# mainbrd.net
KiCad netlist of a schematic drawn in EAGLE
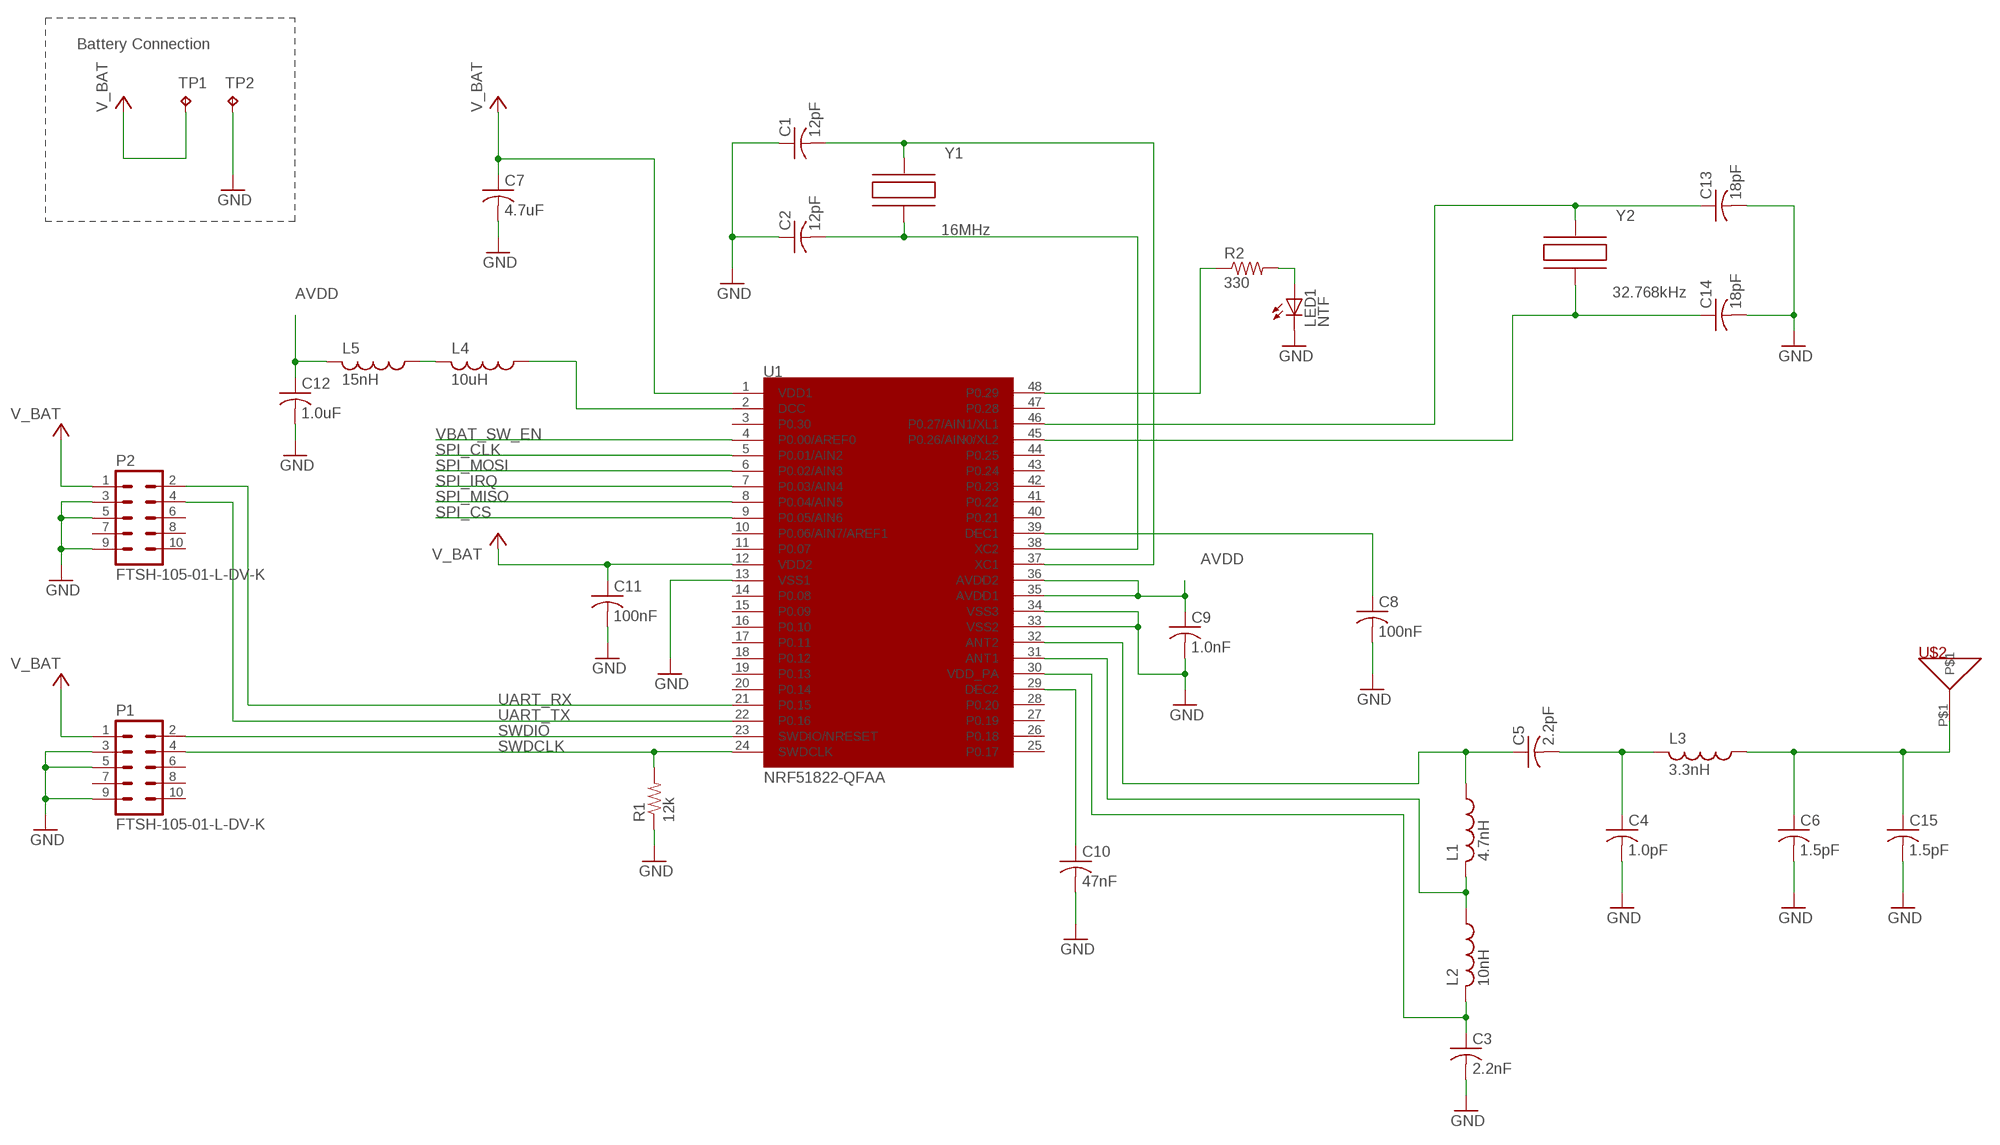
[diagram p0: schematic, sheet 1]
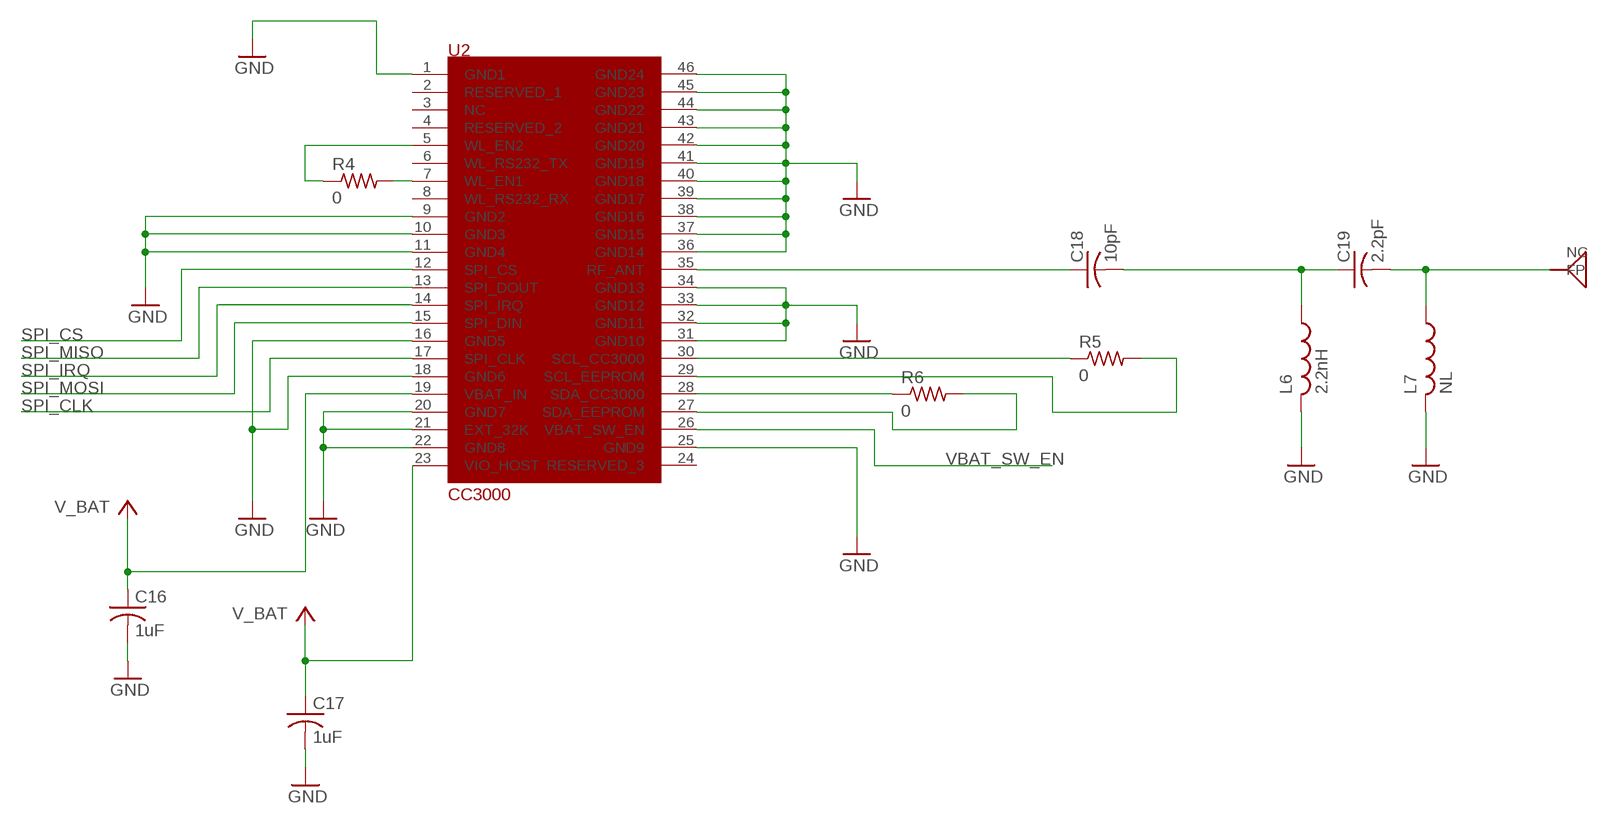
[diagram p1: schematic, sheet 2]

(export (version "E")
  (design (tool "Eeschema 10.0.6"))
  (components
    (comp (ref "C1")
      (value "12pF")
      (footprint "eagle-import:C0402")
      (libsource (lib "eagle-import") (part "C-USC0402"))
    )
    (comp (ref "C2")
      (value "12pF")
      (footprint "eagle-import:C0402")
      (libsource (lib "eagle-import") (part "C-USC0402"))
    )
    (comp (ref "C3")
      (value "2.2nF")
      (footprint "eagle-import:C0402")
      (libsource (lib "eagle-import") (part "C-USC0402"))
    )
    (comp (ref "C4")
      (value "1.0pF")
      (footprint "eagle-import:C0402")
      (libsource (lib "eagle-import") (part "C-USC0402"))
    )
    (comp (ref "C5")
      (value "2.2pF")
      (footprint "eagle-import:C0402")
      (libsource (lib "eagle-import") (part "C-USC0402"))
    )
    (comp (ref "C6")
      (value "1.5pF")
      (footprint "eagle-import:C0402")
      (libsource (lib "eagle-import") (part "C-USC0402"))
    )
    (comp (ref "C7")
      (value "4.7uF")
      (footprint "eagle-import:C0603")
      (libsource (lib "eagle-import") (part "C-USC0603"))
    )
    (comp (ref "C8")
      (value "100nF")
      (footprint "eagle-import:C0402")
      (libsource (lib "eagle-import") (part "C-USC0402"))
    )
    (comp (ref "C9")
      (value "1.0nF")
      (footprint "eagle-import:C0402")
      (libsource (lib "eagle-import") (part "C-USC0402"))
    )
    (comp (ref "C10")
      (value "47nF")
      (footprint "eagle-import:C0402")
      (libsource (lib "eagle-import") (part "C-USC0402"))
    )
    (comp (ref "C11")
      (value "100nF")
      (footprint "eagle-import:C0402")
      (libsource (lib "eagle-import") (part "C-USC0402"))
    )
    (comp (ref "C12")
      (value "1.0uF")
      (footprint "eagle-import:C0603")
      (libsource (lib "eagle-import") (part "C-USC0603"))
    )
    (comp (ref "C13")
      (value "18pF")
      (footprint "eagle-import:C0402")
      (libsource (lib "eagle-import") (part "C-USC0402"))
    )
    (comp (ref "C14")
      (value "18pF")
      (footprint "eagle-import:C0402")
      (libsource (lib "eagle-import") (part "C-USC0402"))
    )
    (comp (ref "C15")
      (value "1.5pF")
      (footprint "eagle-import:C0402")
      (libsource (lib "eagle-import") (part "C-USC0402"))
    )
    (comp (ref "L1")
      (value "4.7nH")
      (footprint "eagle-import:L0402")
      (libsource (lib "eagle-import") (part "L-USL0402"))
    )
    (comp (ref "L2")
      (value "10nH")
      (footprint "eagle-import:L0402")
      (libsource (lib "eagle-import") (part "L-USL0402"))
    )
    (comp (ref "L3")
      (value "3.3nH")
      (footprint "eagle-import:L0402")
      (libsource (lib "eagle-import") (part "L-USL0402"))
    )
    (comp (ref "L4")
      (value "10uH")
      (footprint "eagle-import:L0603")
      (libsource (lib "eagle-import") (part "L-USL0603"))
    )
    (comp (ref "L5")
      (value "15nH")
      (footprint "eagle-import:L0402")
      (libsource (lib "eagle-import") (part "L-USL0402"))
    )
    (comp (ref "LED1")
      (value "NTF")
      (footprint "eagle-import:CHIP-LED0603")
      (libsource (lib "eagle-import") (part "LEDCHIP-LED0603"))
    )
    (comp (ref "P1")
      (value "FTSH-105-01-L-DV-K")
      (footprint "eagle-import:FTSH-105-01-L-DV-K")
      (libsource (lib "eagle-import") (part "FTSH-105-01-L-DV-K"))
    )
    (comp (ref "P2")
      (value "FTSH-105-01-L-DV-K")
      (footprint "eagle-import:FTSH-105-01-L-DV-K")
      (libsource (lib "eagle-import") (part "FTSH-105-01-L-DV-K"))
    )
    (comp (ref "R1")
      (value "12k")
      (footprint "eagle-import:R0402")
      (libsource (lib "eagle-import") (part "rcl2_R-US_R0402"))
    )
    (comp (ref "R2")
      (value "330")
      (footprint "eagle-import:R0402")
      (libsource (lib "eagle-import") (part "rcl2_R-US_R0402"))
    )
    (comp (ref "TP1")
      (value "TPPAD1-13")
      (footprint "eagle-import:P1-13")
      (libsource (lib "eagle-import") (part "TPPAD1-13"))
    )
    (comp (ref "TP2")
      (value "TPPAD1-13")
      (footprint "eagle-import:P1-13")
      (libsource (lib "eagle-import") (part "TPPAD1-13"))
    )
    (comp (ref "U$2")
      (value "PCB_ANT")
      (footprint "eagle-import:PCB_ANT")
      (libsource (lib "eagle-import") (part "PCB_ANT"))
    )
    (comp (ref "U1")
      (value "NRF51822-QFAA")
      (footprint "eagle-import:QFN48")
      (libsource (lib "eagle-import") (part "NRF51822-QFAA"))
    )
    (comp (ref "Y1")
      (value "16MHz")
      (footprint "eagle-import:SMD_3225")
      (libsource (lib "eagle-import") (part "T7V"))
    )
    (comp (ref "Y2")
      (value "32.768kHz")
      (footprint "eagle-import:ECX-39")
      (libsource (lib "eagle-import") (part "ECX_39"))
    )
    (comp (ref "C16")
      (value "1uF")
      (footprint "eagle-import:C0402")
      (libsource (lib "eagle-import") (part "rcl2_C-USC0402"))
    )
    (comp (ref "C17")
      (value "1uF")
      (footprint "eagle-import:C0402")
      (libsource (lib "eagle-import") (part "rcl2_C-USC0402"))
    )
    (comp (ref "C18")
      (value "10pF")
      (footprint "eagle-import:C0402")
      (libsource (lib "eagle-import") (part "rcl2_C-USC0402"))
    )
    (comp (ref "C19")
      (value "2.2pF")
      (footprint "eagle-import:C0402")
      (libsource (lib "eagle-import") (part "rcl2_C-USC0402"))
    )
    (comp (ref "L6")
      (value "2.2nH")
      (footprint "eagle-import:L0402")
      (libsource (lib "eagle-import") (part "L-USL0402"))
    )
    (comp (ref "L7")
      (value "NL")
      (footprint "eagle-import:L0402")
      (libsource (lib "eagle-import") (part "L-USL0402"))
    )
    (comp (ref "R4")
      (value "0")
      (footprint "eagle-import:R0402")
      (libsource (lib "eagle-import") (part "R-US_R0402"))
    )
    (comp (ref "R5")
      (value "0")
      (footprint "eagle-import:R0402")
      (libsource (lib "eagle-import") (part "R-US_R0402"))
    )
    (comp (ref "R6")
      (value "0")
      (footprint "eagle-import:R0402")
      (libsource (lib "eagle-import") (part "R-US_R0402"))
    )
    (comp (ref "U$1")
      (value "AT8010")
      (footprint "eagle-import:AT8010")
      (libsource (lib "eagle-import") (part "AT8010"))
    )
    (comp (ref "U2")
      (value "CC3000")
      (footprint "eagle-import:CC3000")
      (libsource (lib "eagle-import") (part "CC3000"))
    )
  )
  (nets
    (net (code "1") (name "AVDD") (class "Default")
      (node (ref "C12") (pin "1") (pinfunction "1_1") (pintype "passive"))
      (node (ref "C9") (pin "1") (pinfunction "1_1") (pintype "passive"))
      (node (ref "L5") (pin "2") (pinfunction "2_2") (pintype "passive"))
      (node (ref "U1") (pin "35") (pinfunction "AVDD1_35") (pintype "power_in"))
      (node (ref "U1") (pin "36") (pinfunction "AVDD2_36") (pintype "power_in"))
    )
    (net (code "2") (name "GND") (class "Default")
      (node (ref "C1") (pin "1") (pinfunction "1_1") (pintype "passive"))
      (node (ref "C10") (pin "2") (pinfunction "2_2") (pintype "passive"))
      (node (ref "C11") (pin "2") (pinfunction "2_2") (pintype "passive"))
      (node (ref "C12") (pin "2") (pinfunction "2_2") (pintype "passive"))
      (node (ref "C13") (pin "2") (pinfunction "2_2") (pintype "passive"))
      (node (ref "C14") (pin "2") (pinfunction "2_2") (pintype "passive"))
      (node (ref "C15") (pin "2") (pinfunction "2_2") (pintype "passive"))
      (node (ref "C16") (pin "2") (pinfunction "2_2") (pintype "passive"))
      (node (ref "C17") (pin "2") (pinfunction "2_2") (pintype "passive"))
      (node (ref "C2") (pin "1") (pinfunction "1_1") (pintype "passive"))
      (node (ref "C3") (pin "2") (pinfunction "2_2") (pintype "passive"))
      (node (ref "C4") (pin "2") (pinfunction "2_2") (pintype "passive"))
      (node (ref "C6") (pin "2") (pinfunction "2_2") (pintype "passive"))
      (node (ref "C7") (pin "2") (pinfunction "2_2") (pintype "passive"))
      (node (ref "C8") (pin "2") (pinfunction "2_2") (pintype "passive"))
      (node (ref "C9") (pin "2") (pinfunction "2_2") (pintype "passive"))
      (node (ref "L6") (pin "2") (pinfunction "2_2") (pintype "passive"))
      (node (ref "L7") (pin "2") (pinfunction "2_2") (pintype "passive"))
      (node (ref "LED1") (pin "C") (pinfunction "C_C") (pintype "passive"))
      (node (ref "P1") (pin "3") (pinfunction "3_3") (pintype "passive"))
      (node (ref "P1") (pin "5") (pinfunction "5_5") (pintype "passive"))
      (node (ref "P1") (pin "9") (pinfunction "9_9") (pintype "passive"))
      (node (ref "P2") (pin "3") (pinfunction "3_3") (pintype "passive"))
      (node (ref "P2") (pin "5") (pinfunction "5_5") (pintype "passive"))
      (node (ref "P2") (pin "9") (pinfunction "9_9") (pintype "passive"))
      (node (ref "R1") (pin "1") (pinfunction "1_1") (pintype "passive"))
      (node (ref "TP2") (pin "TP") (pinfunction "TP_TP") (pintype "bidirectional"))
      (node (ref "U1") (pin "13") (pinfunction "VSS1_13") (pintype "power_in"))
      (node (ref "U1") (pin "33") (pinfunction "VSS2_33") (pintype "bidirectional"))
      (node (ref "U1") (pin "34") (pinfunction "VSS3_34") (pintype "bidirectional"))
      (node (ref "U2") (pin "1") (pinfunction "GND1_1") (pintype "power_in"))
      (node (ref "U2") (pin "10") (pinfunction "GND3_10") (pintype "power_in"))
      (node (ref "U2") (pin "11") (pinfunction "GND4_11") (pintype "bidirectional"))
      (node (ref "U2") (pin "16") (pinfunction "GND5_16") (pintype "power_in"))
      (node (ref "U2") (pin "18") (pinfunction "GND6_18") (pintype "power_in"))
      (node (ref "U2") (pin "20") (pinfunction "GND7_20") (pintype "power_in"))
      (node (ref "U2") (pin "21") (pinfunction "EXT_32K_21") (pintype "power_in"))
      (node (ref "U2") (pin "22") (pinfunction "GND8_22") (pintype "power_in"))
      (node (ref "U2") (pin "25") (pinfunction "GND9_25") (pintype "power_in"))
      (node (ref "U2") (pin "31") (pinfunction "GND10_31") (pintype "bidirectional"))
      (node (ref "U2") (pin "32") (pinfunction "GND11_32") (pintype "bidirectional"))
      (node (ref "U2") (pin "33") (pinfunction "GND12_33") (pintype "bidirectional"))
      (node (ref "U2") (pin "34") (pinfunction "GND13_34") (pintype "bidirectional"))
      (node (ref "U2") (pin "36") (pinfunction "GND14_36") (pintype "power_in"))
      (node (ref "U2") (pin "37") (pinfunction "GND15_37") (pintype "power_in"))
      (node (ref "U2") (pin "38") (pinfunction "GND16_38") (pintype "power_in"))
      (node (ref "U2") (pin "39") (pinfunction "GND17_39") (pintype "power_in"))
      (node (ref "U2") (pin "40") (pinfunction "GND18_40") (pintype "power_in"))
      (node (ref "U2") (pin "41") (pinfunction "GND19_41") (pintype "power_in"))
      (node (ref "U2") (pin "42") (pinfunction "GND20_42") (pintype "power_in"))
      (node (ref "U2") (pin "43") (pinfunction "GND21_43") (pintype "power_in"))
      (node (ref "U2") (pin "44") (pinfunction "GND22_44") (pintype "power_in"))
      (node (ref "U2") (pin "45") (pinfunction "GND23_45") (pintype "power_in"))
      (node (ref "U2") (pin "46") (pinfunction "GND24_46") (pintype "power_in"))
      (node (ref "U2") (pin "9") (pinfunction "GND2_9") (pintype "power_in"))
    )
    (net (code "3") (name "Net-(C4-Pad1)") (class "Default")
      (node (ref "C4") (pin "1") (pinfunction "1_1") (pintype "passive"))
      (node (ref "C5") (pin "2") (pinfunction "2_2") (pintype "passive"))
      (node (ref "L3") (pin "2") (pinfunction "2_2") (pintype "passive"))
    )
    (net (code "4") (name "Net-(C15-Pad1)") (class "Default")
      (node (ref "C15") (pin "1") (pinfunction "1_1") (pintype "passive"))
      (node (ref "C6") (pin "1") (pinfunction "1_1") (pintype "passive"))
      (node (ref "L3") (pin "1") (pinfunction "1_1") (pintype "passive"))
      (node (ref "U$2") (pin "P$1") (pinfunction "P$1_P$1") (pintype "bidirectional"))
    )
    (net (code "5") (name "Net-(C18-Pad2)") (class "Default")
      (node (ref "C18") (pin "2") (pinfunction "2_2") (pintype "passive"))
      (node (ref "C19") (pin "1") (pinfunction "1_1") (pintype "passive"))
      (node (ref "L6") (pin "1") (pinfunction "1_1") (pintype "passive"))
    )
    (net (code "6") (name "Net-(C19-Pad2)") (class "Default")
      (node (ref "C19") (pin "2") (pinfunction "2_2") (pintype "passive"))
      (node (ref "L7") (pin "1") (pinfunction "1_1") (pintype "passive"))
      (node (ref "U$1") (pin "FP") (pinfunction "FP_FP") (pintype "bidirectional"))
    )
    (net (code "7") (name "Net-(L4-Pad2)") (class "Default")
      (node (ref "L4") (pin "2") (pinfunction "2_2") (pintype "passive"))
      (node (ref "L5") (pin "1") (pinfunction "1_1") (pintype "passive"))
    )
    (net (code "8") (name "Net-(LED1-PadA)") (class "Default")
      (node (ref "LED1") (pin "A") (pinfunction "A_A") (pintype "passive"))
      (node (ref "R2") (pin "2") (pinfunction "2_2") (pintype "passive"))
    )
    (net (code "9") (name "Net-(U1-ANT1)") (class "Default")
      (node (ref "L1") (pin "2") (pinfunction "2_2") (pintype "passive"))
      (node (ref "L2") (pin "1") (pinfunction "1_1") (pintype "passive"))
      (node (ref "U1") (pin "31") (pinfunction "ANT1_31") (pintype "bidirectional"))
    )
    (net (code "10") (name "Net-(U1-ANT2)") (class "Default")
      (node (ref "C5") (pin "1") (pinfunction "1_1") (pintype "passive"))
      (node (ref "L1") (pin "1") (pinfunction "1_1") (pintype "passive"))
      (node (ref "U1") (pin "32") (pinfunction "ANT2_32") (pintype "bidirectional"))
    )
    (net (code "11") (name "Net-(U1-DCC)") (class "Default")
      (node (ref "L4") (pin "1") (pinfunction "1_1") (pintype "passive"))
      (node (ref "U1") (pin "2") (pinfunction "DCC_2") (pintype "power_in"))
    )
    (net (code "12") (name "Net-(U1-DEC1)") (class "Default")
      (node (ref "C8") (pin "1") (pinfunction "1_1") (pintype "passive"))
      (node (ref "U1") (pin "39") (pinfunction "DEC1_39") (pintype "bidirectional"))
    )
    (net (code "13") (name "Net-(U1-DEC2)") (class "Default")
      (node (ref "C10") (pin "1") (pinfunction "1_1") (pintype "passive"))
      (node (ref "U1") (pin "29") (pinfunction "DEC2_29") (pintype "bidirectional"))
    )
    (net (code "14") (name "Net-(U1-P0.26{slash}AIN0{slash}XL2)") (class "Default")
      (node (ref "C14") (pin "1") (pinfunction "1_1") (pintype "passive"))
      (node (ref "U1") (pin "45") (pinfunction "P0.26/AIN0/XL2_45") (pintype "bidirectional"))
      (node (ref "Y2") (pin "1") (pinfunction "P$1_1") (pintype "bidirectional"))
    )
    (net (code "15") (name "Net-(U1-P0.27{slash}AIN1{slash}XL1)") (class "Default")
      (node (ref "C13") (pin "1") (pinfunction "1_1") (pintype "passive"))
      (node (ref "U1") (pin "46") (pinfunction "P0.27/AIN1/XL1_46") (pintype "bidirectional"))
      (node (ref "Y2") (pin "2") (pinfunction "P$2_2") (pintype "bidirectional"))
    )
    (net (code "16") (name "Net-(U1-P0.29)") (class "Default")
      (node (ref "R2") (pin "1") (pinfunction "1_1") (pintype "passive"))
      (node (ref "U1") (pin "48") (pinfunction "P0.29_48") (pintype "bidirectional"))
    )
    (net (code "17") (name "Net-(U1-VDD_PA)") (class "Default")
      (node (ref "C3") (pin "1") (pinfunction "1_1") (pintype "passive"))
      (node (ref "L2") (pin "2") (pinfunction "2_2") (pintype "passive"))
      (node (ref "U1") (pin "30") (pinfunction "VDD_PA_30") (pintype "power_in"))
    )
    (net (code "18") (name "Net-(U1-XC1)") (class "Default")
      (node (ref "C1") (pin "2") (pinfunction "2_2") (pintype "passive"))
      (node (ref "U1") (pin "37") (pinfunction "XC1_37") (pintype "bidirectional"))
      (node (ref "Y1") (pin "3") (pinfunction "P$2_3") (pintype "bidirectional"))
    )
    (net (code "19") (name "Net-(U1-XC2)") (class "Default")
      (node (ref "C2") (pin "2") (pinfunction "2_2") (pintype "passive"))
      (node (ref "U1") (pin "38") (pinfunction "XC2_38") (pintype "bidirectional"))
      (node (ref "Y1") (pin "1") (pinfunction "P$1_1") (pintype "bidirectional"))
    )
    (net (code "20") (name "Net-(U2-RF_ANT)") (class "Default")
      (node (ref "C18") (pin "1") (pinfunction "1_1") (pintype "passive"))
      (node (ref "U2") (pin "35") (pinfunction "RF_ANT_35") (pintype "bidirectional"))
    )
    (net (code "21") (name "Net-(U2-SCL_CC3000)") (class "Default")
      (node (ref "R5") (pin "1") (pinfunction "1_1") (pintype "passive"))
      (node (ref "U2") (pin "30") (pinfunction "SCL_CC3000_30") (pintype "bidirectional"))
    )
    (net (code "22") (name "Net-(U2-SCL_EEPROM)") (class "Default")
      (node (ref "R5") (pin "2") (pinfunction "2_2") (pintype "passive"))
      (node (ref "U2") (pin "29") (pinfunction "SCL_EEPROM_29") (pintype "bidirectional"))
    )
    (net (code "23") (name "Net-(U2-SDA_CC3000)") (class "Default")
      (node (ref "R6") (pin "1") (pinfunction "1_1") (pintype "passive"))
      (node (ref "U2") (pin "28") (pinfunction "SDA_CC3000_28") (pintype "bidirectional"))
    )
    (net (code "24") (name "Net-(U2-SDA_EEPROM)") (class "Default")
      (node (ref "R6") (pin "2") (pinfunction "2_2") (pintype "passive"))
      (node (ref "U2") (pin "27") (pinfunction "SDA_EEPROM_27") (pintype "bidirectional"))
    )
    (net (code "25") (name "Net-(U2-WL_EN1)") (class "Default")
      (node (ref "R4") (pin "2") (pinfunction "2_2") (pintype "passive"))
      (node (ref "U2") (pin "7") (pinfunction "WL_EN1_7") (pintype "input"))
    )
    (net (code "26") (name "Net-(U2-WL_EN2)") (class "Default")
      (node (ref "R4") (pin "1") (pinfunction "1_1") (pintype "passive"))
      (node (ref "U2") (pin "5") (pinfunction "WL_EN2_5") (pintype "input"))
    )
    (net (code "27") (name "SPI_CLK") (class "Default")
      (node (ref "U1") (pin "5") (pinfunction "P0.01/AIN2_5") (pintype "bidirectional"))
      (node (ref "U2") (pin "17") (pinfunction "SPI_CLK_17") (pintype "input"))
    )
    (net (code "28") (name "SPI_CS") (class "Default")
      (node (ref "U1") (pin "9") (pinfunction "P0.05/AIN6_9") (pintype "bidirectional"))
      (node (ref "U2") (pin "12") (pinfunction "SPI_CS_12") (pintype "input"))
    )
    (net (code "29") (name "SPI_IRQ") (class "Default")
      (node (ref "U1") (pin "7") (pinfunction "P0.03/AIN4_7") (pintype "bidirectional"))
      (node (ref "U2") (pin "14") (pinfunction "SPI_IRQ_14") (pintype "output"))
    )
    (net (code "30") (name "SPI_MISO") (class "Default")
      (node (ref "U1") (pin "8") (pinfunction "P0.04/AIN5_8") (pintype "bidirectional"))
      (node (ref "U2") (pin "13") (pinfunction "SPI_DOUT_13") (pintype "output"))
    )
    (net (code "31") (name "SPI_MOSI") (class "Default")
      (node (ref "U1") (pin "6") (pinfunction "P0.02/AIN3_6") (pintype "bidirectional"))
      (node (ref "U2") (pin "15") (pinfunction "SPI_DIN_15") (pintype "input"))
    )
    (net (code "32") (name "SWDCLK") (class "Default")
      (node (ref "P1") (pin "4") (pinfunction "4_4") (pintype "passive"))
      (node (ref "R1") (pin "2") (pinfunction "2_2") (pintype "passive"))
      (node (ref "U1") (pin "24") (pinfunction "SWDCLK_24") (pintype "bidirectional"))
    )
    (net (code "33") (name "SWDIO") (class "Default")
      (node (ref "P1") (pin "2") (pinfunction "2_2") (pintype "passive"))
      (node (ref "U1") (pin "23") (pinfunction "SWDIO/NRESET_23") (pintype "bidirectional"))
    )
    (net (code "34") (name "UART_RX") (class "Default")
      (node (ref "P2") (pin "2") (pinfunction "2_2") (pintype "passive"))
      (node (ref "U1") (pin "21") (pinfunction "P0.15_21") (pintype "bidirectional"))
    )
    (net (code "35") (name "UART_TX") (class "Default")
      (node (ref "P2") (pin "4") (pinfunction "4_4") (pintype "passive"))
      (node (ref "U1") (pin "22") (pinfunction "P0.16_22") (pintype "bidirectional"))
    )
    (net (code "36") (name "VBAT_SW_EN") (class "Default")
      (node (ref "U1") (pin "4") (pinfunction "P0.00/AREF0_4") (pintype "bidirectional"))
      (node (ref "U2") (pin "26") (pinfunction "VBAT_SW_EN_26") (pintype "input"))
    )
    (net (code "37") (name "VCC") (class "Default")
      (node (ref "C11") (pin "1") (pinfunction "1_1") (pintype "passive"))
      (node (ref "C16") (pin "1") (pinfunction "1_1") (pintype "passive"))
      (node (ref "C17") (pin "1") (pinfunction "1_1") (pintype "passive"))
      (node (ref "C7") (pin "1") (pinfunction "1_1") (pintype "passive"))
      (node (ref "P1") (pin "1") (pinfunction "1_1") (pintype "passive"))
      (node (ref "P2") (pin "1") (pinfunction "1_1") (pintype "passive"))
      (node (ref "TP1") (pin "TP") (pinfunction "TP_TP") (pintype "bidirectional"))
      (node (ref "U1") (pin "1") (pinfunction "VDD1_1") (pintype "power_in"))
      (node (ref "U1") (pin "12") (pinfunction "VDD2_12") (pintype "power_in"))
      (node (ref "U2") (pin "19") (pinfunction "VBAT_IN_19") (pintype "power_in"))
      (node (ref "U2") (pin "23") (pinfunction "VIO_HOST_23") (pintype "power_in"))
    )
    (net (code "38") (name "unconnected-(P1-Pad6)") (class "Default")
      (node (ref "P1") (pin "6") (pinfunction "6_6") (pintype "passive"))
    )
    (net (code "39") (name "unconnected-(P1-Pad7)") (class "Default")
      (node (ref "P1") (pin "7") (pinfunction "7_7") (pintype "passive"))
    )
    (net (code "40") (name "unconnected-(P1-Pad8)") (class "Default")
      (node (ref "P1") (pin "8") (pinfunction "8_8") (pintype "passive"))
    )
    (net (code "41") (name "unconnected-(P1-Pad10)") (class "Default")
      (node (ref "P1") (pin "10") (pinfunction "10_10") (pintype "passive"))
    )
    (net (code "42") (name "unconnected-(P2-Pad6)") (class "Default")
      (node (ref "P2") (pin "6") (pinfunction "6_6") (pintype "passive"))
    )
    (net (code "43") (name "unconnected-(P2-Pad7)") (class "Default")
      (node (ref "P2") (pin "7") (pinfunction "7_7") (pintype "passive"))
    )
    (net (code "44") (name "unconnected-(P2-Pad8)") (class "Default")
      (node (ref "P2") (pin "8") (pinfunction "8_8") (pintype "passive"))
    )
    (net (code "45") (name "unconnected-(P2-Pad10)") (class "Default")
      (node (ref "P2") (pin "10") (pinfunction "10_10") (pintype "passive"))
    )
    (net (code "46") (name "unconnected-(U$1-PadNC)") (class "Default")
      (node (ref "U$1") (pin "NC") (pinfunction "NC_NC") (pintype "no_connect"))
    )
    (net (code "47") (name "unconnected-(U1-P0.06{slash}AIN7{slash}AREF1-Pad10)") (class "Default")
      (node (ref "U1") (pin "10") (pinfunction "P0.06/AIN7/AREF1_10") (pintype "bidirectional"))
    )
    (net (code "48") (name "unconnected-(U1-P0.07-Pad11)") (class "Default")
      (node (ref "U1") (pin "11") (pinfunction "P0.07_11") (pintype "bidirectional"))
    )
    (net (code "49") (name "unconnected-(U1-P0.08-Pad14)") (class "Default")
      (node (ref "U1") (pin "14") (pinfunction "P0.08_14") (pintype "bidirectional"))
    )
    (net (code "50") (name "unconnected-(U1-P0.09-Pad15)") (class "Default")
      (node (ref "U1") (pin "15") (pinfunction "P0.09_15") (pintype "bidirectional"))
    )
    (net (code "51") (name "unconnected-(U1-P0.10-Pad16)") (class "Default")
      (node (ref "U1") (pin "16") (pinfunction "P0.10_16") (pintype "bidirectional"))
    )
    (net (code "52") (name "unconnected-(U1-P0.11-Pad17)") (class "Default")
      (node (ref "U1") (pin "17") (pinfunction "P0.11_17") (pintype "bidirectional"))
    )
    (net (code "53") (name "unconnected-(U1-P0.12-Pad18)") (class "Default")
      (node (ref "U1") (pin "18") (pinfunction "P0.12_18") (pintype "bidirectional"))
    )
    (net (code "54") (name "unconnected-(U1-P0.13-Pad19)") (class "Default")
      (node (ref "U1") (pin "19") (pinfunction "P0.13_19") (pintype "bidirectional"))
    )
    (net (code "55") (name "unconnected-(U1-P0.14-Pad20)") (class "Default")
      (node (ref "U1") (pin "20") (pinfunction "P0.14_20") (pintype "bidirectional"))
    )
    (net (code "56") (name "unconnected-(U1-P0.17-Pad25)") (class "Default")
      (node (ref "U1") (pin "25") (pinfunction "P0.17_25") (pintype "bidirectional"))
    )
    (net (code "57") (name "unconnected-(U1-P0.18-Pad26)") (class "Default")
      (node (ref "U1") (pin "26") (pinfunction "P0.18_26") (pintype "bidirectional"))
    )
    (net (code "58") (name "unconnected-(U1-P0.19-Pad27)") (class "Default")
      (node (ref "U1") (pin "27") (pinfunction "P0.19_27") (pintype "bidirectional"))
    )
    (net (code "59") (name "unconnected-(U1-P0.20-Pad28)") (class "Default")
      (node (ref "U1") (pin "28") (pinfunction "P0.20_28") (pintype "bidirectional"))
    )
    (net (code "60") (name "unconnected-(U1-P0.21-Pad40)") (class "Default")
      (node (ref "U1") (pin "40") (pinfunction "P0.21_40") (pintype "bidirectional"))
    )
    (net (code "61") (name "unconnected-(U1-P0.22-Pad41)") (class "Default")
      (node (ref "U1") (pin "41") (pinfunction "P0.22_41") (pintype "bidirectional"))
    )
    (net (code "62") (name "unconnected-(U1-P0.23-Pad42)") (class "Default")
      (node (ref "U1") (pin "42") (pinfunction "P0.23_42") (pintype "bidirectional"))
    )
    (net (code "63") (name "unconnected-(U1-P0.24-Pad43)") (class "Default")
      (node (ref "U1") (pin "43") (pinfunction "P0.24_43") (pintype "bidirectional"))
    )
    (net (code "64") (name "unconnected-(U1-P0.25-Pad44)") (class "Default")
      (node (ref "U1") (pin "44") (pinfunction "P0.25_44") (pintype "bidirectional"))
    )
    (net (code "65") (name "unconnected-(U1-P0.28-Pad47)") (class "Default")
      (node (ref "U1") (pin "47") (pinfunction "P0.28_47") (pintype "bidirectional"))
    )
    (net (code "66") (name "unconnected-(U1-P0.30-Pad3)") (class "Default")
      (node (ref "U1") (pin "3") (pinfunction "P0.30_3") (pintype "bidirectional"))
    )
    (net (code "67") (name "unconnected-(U2-NC-Pad3)") (class "Default")
      (node (ref "U2") (pin "3") (pinfunction "NC_3") (pintype "no_connect"))
    )
    (net (code "68") (name "unconnected-(U2-RESERVED_1-Pad2)") (class "Default")
      (node (ref "U2") (pin "2") (pinfunction "RESERVED_1_2") (pintype "bidirectional"))
    )
    (net (code "69") (name "unconnected-(U2-RESERVED_2-Pad4)") (class "Default")
      (node (ref "U2") (pin "4") (pinfunction "RESERVED_2_4") (pintype "bidirectional"))
    )
    (net (code "70") (name "unconnected-(U2-RESERVED_3-Pad24)") (class "Default")
      (node (ref "U2") (pin "24") (pinfunction "RESERVED_3_24") (pintype "output"))
    )
    (net (code "71") (name "unconnected-(U2-WL_RS232_RX-Pad8)") (class "Default")
      (node (ref "U2") (pin "8") (pinfunction "WL_RS232_RX_8") (pintype "input"))
    )
    (net (code "72") (name "unconnected-(U2-WL_RS232_TX-Pad6)") (class "Default")
      (node (ref "U2") (pin "6") (pinfunction "WL_RS232_TX_6") (pintype "output"))
    )
  )
)
